# RF.net
KiCad netlist of a schematic drawn in EAGLE
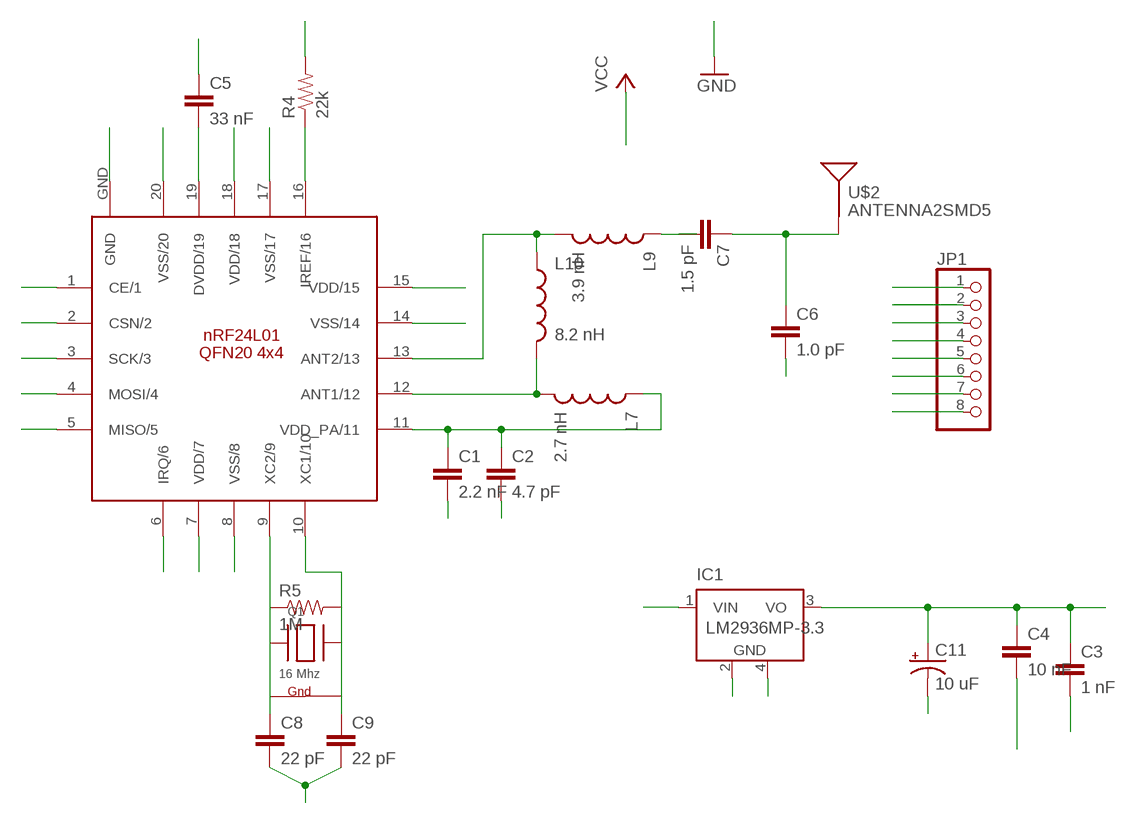
[diagram p0: schematic, sheet 1]

(export (version "E")
  (design (tool "Eeschema 10.0.6"))
  (components
    (comp (ref "C1")
      (value "2.2 nF")
      (footprint "eagle-import:0805")
      (libsource (lib "eagle-import") (part "CAP0805"))
    )
    (comp (ref "C2")
      (value "4.7 pF")
      (footprint "eagle-import:0805")
      (libsource (lib "eagle-import") (part "CAP0805"))
    )
    (comp (ref "C3")
      (value "1 nF")
      (footprint "eagle-import:0805")
      (libsource (lib "eagle-import") (part "CAP0805"))
    )
    (comp (ref "C4")
      (value "10 nF")
      (footprint "eagle-import:0805")
      (libsource (lib "eagle-import") (part "CAP0805"))
    )
    (comp (ref "C5")
      (value "33 nF")
      (footprint "eagle-import:0805")
      (libsource (lib "eagle-import") (part "CAP0805"))
    )
    (comp (ref "C6")
      (value "1.0 pF")
      (footprint "eagle-import:0805")
      (libsource (lib "eagle-import") (part "CAP0805"))
    )
    (comp (ref "C7")
      (value "1.5 pF")
      (footprint "eagle-import:0805")
      (libsource (lib "eagle-import") (part "CAP0805"))
    )
    (comp (ref "C8")
      (value "22 pF")
      (footprint "eagle-import:0805")
      (libsource (lib "eagle-import") (part "CAP0805"))
    )
    (comp (ref "C9")
      (value "22 pF")
      (footprint "eagle-import:0805")
      (libsource (lib "eagle-import") (part "CAP0805"))
    )
    (comp (ref "C11")
      (value "10 uF")
      (footprint "eagle-import:EIA3216")
      (libsource (lib "eagle-import") (part "CAP_POL1206"))
    )
    (comp (ref "IC1")
      (value "LM2936MP-3.3")
      (footprint "eagle-import:SOT223")
      (fields (field (name "MF") "NATIONAL SEMICONDUCTOR") (field (name "MPN") "LM2936MP-3.3/NOPB"))
      (libsource (lib "eagle-import") (part "LM2936MP?-3.3"))
    )
    (comp (ref "JP1")
      (value "PINHD-1X8BIG")
      (footprint "eagle-import:1X08-BIG")
      (libsource (lib "eagle-import") (part "PINHD-1X8BIG"))
    )
    (comp (ref "L7")
      (value "2.7 nH")
      (footprint "eagle-import:C0402")
      (libsource (lib "eagle-import") (part "INDUCTOR0402"))
    )
    (comp (ref "L9")
      (value "3.9 nH")
      (footprint "eagle-import:C0402")
      (libsource (lib "eagle-import") (part "INDUCTOR0402"))
    )
    (comp (ref "L10")
      (value "8.2 nH")
      (footprint "eagle-import:C0402")
      (libsource (lib "eagle-import") (part "INDUCTOR0402"))
    )
    (comp (ref "Q1")
      (value "16 Mhz")
      (footprint "eagle-import:NX3225")
      (libsource (lib "eagle-import") (part "XTAL-4-3225"))
    )
    (comp (ref "R4")
      (value "22k")
      (footprint "eagle-import:0805")
      (libsource (lib "eagle-import") (part "RESISTOR0805-RES"))
    )
    (comp (ref "R5")
      (value "1M")
      (footprint "eagle-import:0805")
      (libsource (lib "eagle-import") (part "RESISTOR0805-RES"))
    )
    (comp (ref "U$1")
      (value "NRF24L01")
      (footprint "eagle-import:QFN20(4X4)")
      (libsource (lib "eagle-import") (part "NRF24L01"))
    )
    (comp (ref "U$2")
      (value "ANTENNA2SMD5")
      (footprint "eagle-import:ANTENNA-CHIP5")
      (libsource (lib "eagle-import") (part "ANTENNA2SMD5"))
    )
  )
  (nets
    (net (code "1") (name "/CE") (class "Default")
      (node (ref "JP1") (pin "2") (pinfunction "2_2") (pintype "passive"))
      (node (ref "U$1") (pin "1") (pinfunction "CE/1_1") (pintype "bidirectional"))
    )
    (net (code "2") (name "/CSN") (class "Default")
      (node (ref "JP1") (pin "3") (pinfunction "3_3") (pintype "passive"))
      (node (ref "U$1") (pin "2") (pinfunction "CSN/2_2") (pintype "bidirectional"))
    )
    (net (code "3") (name "/G1") (class "Default")
      (node (ref "Q1") (pin "4") (pinfunction "G1_4") (pintype "power_in"))
    )
    (net (code "4") (name "/G2") (class "Default")
      (node (ref "Q1") (pin "2") (pinfunction "G2_2") (pintype "power_in"))
    )
    (net (code "5") (name "/IQR") (class "Default")
      (node (ref "JP1") (pin "7") (pinfunction "7_7") (pintype "passive"))
      (node (ref "U$1") (pin "6") (pinfunction "IRQ/6_6") (pintype "bidirectional"))
    )
    (net (code "6") (name "/MISO") (class "Default")
      (node (ref "JP1") (pin "6") (pinfunction "6_6") (pintype "passive"))
      (node (ref "U$1") (pin "5") (pinfunction "MISO/5_5") (pintype "bidirectional"))
    )
    (net (code "7") (name "/MOSI") (class "Default")
      (node (ref "JP1") (pin "5") (pinfunction "5_5") (pintype "passive"))
      (node (ref "U$1") (pin "4") (pinfunction "MOSI/4_4") (pintype "bidirectional"))
    )
    (net (code "8") (name "/SCK") (class "Default")
      (node (ref "JP1") (pin "4") (pinfunction "4_4") (pintype "passive"))
      (node (ref "U$1") (pin "3") (pinfunction "SCK/3_3") (pintype "bidirectional"))
    )
    (net (code "9") (name "/VDD") (class "Default")
      (node (ref "C11") (pin "A") (pinfunction "+_A") (pintype "passive"))
      (node (ref "C3") (pin "1") (pinfunction "1_1") (pintype "passive"))
      (node (ref "C4") (pin "1") (pinfunction "1_1") (pintype "passive"))
      (node (ref "IC1") (pin "3") (pinfunction "VO_3") (pintype "passive"))
      (node (ref "JP1") (pin "1") (pinfunction "1_1") (pintype "passive"))
      (node (ref "U$1") (pin "15") (pinfunction "VDD/15_15") (pintype "bidirectional"))
      (node (ref "U$1") (pin "18") (pinfunction "VDD/18_18") (pintype "bidirectional"))
      (node (ref "U$1") (pin "7") (pinfunction "VDD/7_7") (pintype "bidirectional"))
    )
    (net (code "10") (name "GND") (class "Default")
      (node (ref "C1") (pin "2") (pinfunction "2_2") (pintype "passive"))
      (node (ref "C11") (pin "C") (pinfunction "-_C") (pintype "passive"))
      (node (ref "C2") (pin "2") (pinfunction "2_2") (pintype "passive"))
      (node (ref "C3") (pin "2") (pinfunction "2_2") (pintype "passive"))
      (node (ref "C4") (pin "2") (pinfunction "2_2") (pintype "passive"))
      (node (ref "C5") (pin "1") (pinfunction "1_1") (pintype "passive"))
      (node (ref "C6") (pin "2") (pinfunction "2_2") (pintype "passive"))
      (node (ref "C8") (pin "2") (pinfunction "2_2") (pintype "passive"))
      (node (ref "C9") (pin "2") (pinfunction "2_2") (pintype "passive"))
      (node (ref "IC1") (pin "2") (pinfunction "GND_2") (pintype "passive"))
      (node (ref "IC1") (pin "4") (pinfunction "GND_4") (pintype "passive"))
      (node (ref "JP1") (pin "8") (pinfunction "8_8") (pintype "passive"))
      (node (ref "R4") (pin "2") (pinfunction "2_2") (pintype "passive"))
      (node (ref "U$1") (pin "14") (pinfunction "VSS/14_14") (pintype "bidirectional"))
      (node (ref "U$1") (pin "17") (pinfunction "VSS/17_17") (pintype "bidirectional"))
      (node (ref "U$1") (pin "20") (pinfunction "VSS/20_20") (pintype "bidirectional"))
      (node (ref "U$1") (pin "8") (pinfunction "VSS/8_8") (pintype "bidirectional"))
      (node (ref "U$1") (pin "GND") (pinfunction "GND_GND") (pintype "bidirectional"))
    )
    (net (code "11") (name "Net-(C7-Pad2)") (class "Default")
      (node (ref "C7") (pin "2") (pinfunction "2_2") (pintype "passive"))
      (node (ref "L9") (pin "1") (pinfunction "1_1") (pintype "passive"))
    )
    (net (code "12") (name "Net-(Q1-X1)") (class "Default")
      (node (ref "C8") (pin "1") (pinfunction "1_1") (pintype "passive"))
      (node (ref "Q1") (pin "1") (pinfunction "X1_1") (pintype "bidirectional"))
      (node (ref "R5") (pin "1") (pinfunction "1_1") (pintype "passive"))
      (node (ref "U$1") (pin "9") (pinfunction "XC2/9_9") (pintype "bidirectional"))
    )
    (net (code "13") (name "Net-(Q1-X2)") (class "Default")
      (node (ref "C9") (pin "1") (pinfunction "1_1") (pintype "passive"))
      (node (ref "Q1") (pin "3") (pinfunction "X2_3") (pintype "bidirectional"))
      (node (ref "R5") (pin "2") (pinfunction "2_2") (pintype "passive"))
      (node (ref "U$1") (pin "10") (pinfunction "XC1/10_10") (pintype "bidirectional"))
    )
    (net (code "14") (name "Net-(U$1-ANT1{slash}12)") (class "Default")
      (node (ref "L10") (pin "2") (pinfunction "2_2") (pintype "passive"))
      (node (ref "L7") (pin "2") (pinfunction "2_2") (pintype "passive"))
      (node (ref "U$1") (pin "12") (pinfunction "ANT1/12_12") (pintype "bidirectional"))
    )
    (net (code "15") (name "Net-(U$1-ANT2{slash}13)") (class "Default")
      (node (ref "L10") (pin "1") (pinfunction "1_1") (pintype "passive"))
      (node (ref "L9") (pin "2") (pinfunction "2_2") (pintype "passive"))
      (node (ref "U$1") (pin "13") (pinfunction "ANT2/13_13") (pintype "bidirectional"))
    )
    (net (code "16") (name "Net-(U$1-DVDD{slash}19)") (class "Default")
      (node (ref "C5") (pin "2") (pinfunction "2_2") (pintype "passive"))
      (node (ref "U$1") (pin "19") (pinfunction "DVDD/19_19") (pintype "bidirectional"))
    )
    (net (code "17") (name "Net-(U$1-IREF{slash}16)") (class "Default")
      (node (ref "R4") (pin "1") (pinfunction "1_1") (pintype "passive"))
      (node (ref "U$1") (pin "16") (pinfunction "IREF/16_16") (pintype "bidirectional"))
    )
    (net (code "18") (name "Net-(U$1-VDD_PA{slash}11)") (class "Default")
      (node (ref "C1") (pin "1") (pinfunction "1_1") (pintype "passive"))
      (node (ref "C2") (pin "1") (pinfunction "1_1") (pintype "passive"))
      (node (ref "L7") (pin "1") (pinfunction "1_1") (pintype "passive"))
      (node (ref "U$1") (pin "11") (pinfunction "VDD_PA/11_11") (pintype "bidirectional"))
    )
    (net (code "19") (name "Net-(U$2-SIGNAL)") (class "Default")
      (node (ref "C6") (pin "1") (pinfunction "1_1") (pintype "passive"))
      (node (ref "C7") (pin "1") (pinfunction "1_1") (pintype "passive"))
      (node (ref "U$2") (pin "FEED") (pinfunction "SIGNAL_FEED") (pintype "bidirectional"))
    )
    (net (code "20") (name "VCC") (class "Default")
      (node (ref "IC1") (pin "1") (pinfunction "VIN_1") (pintype "input"))
    )
  )
)
